# RTR_2T_LCD_CCS.net
KiCad netlist of a schematic drawn in EAGLE
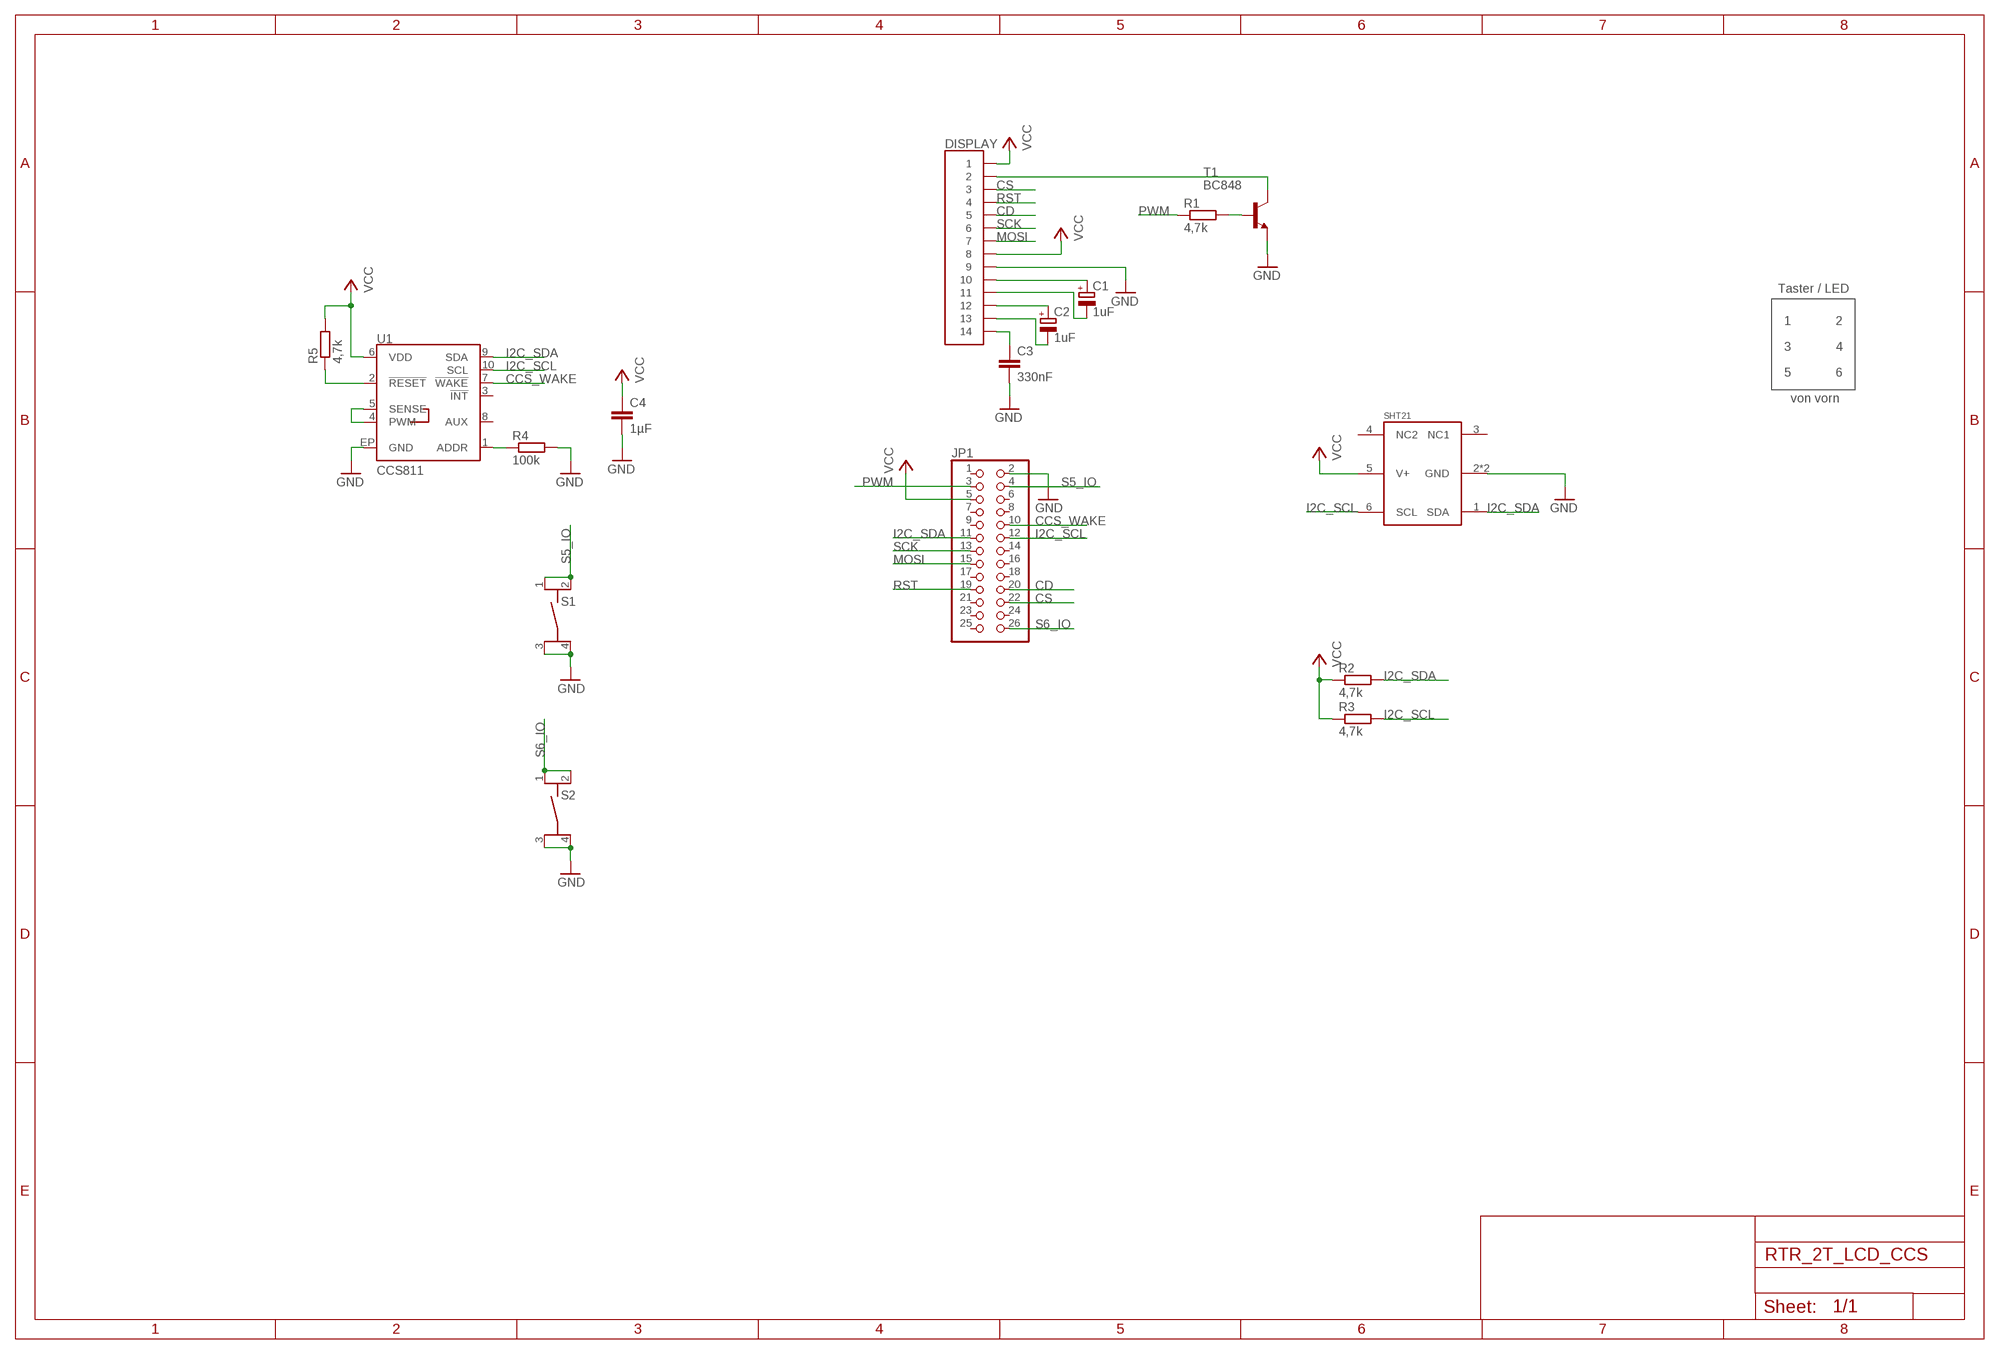
[diagram p0: schematic, sheet 1]

(export (version "E")
  (design (tool "Eeschema 10.0.6"))
  (components
    (comp (ref "C1")
      (value "1uF")
      (footprint "eagle-import:153CLV-0405")
      (libsource (lib "eagle-import") (part "CPOL-EU153CLV-0405"))
    )
    (comp (ref "C2")
      (value "1uF")
      (footprint "eagle-import:153CLV-0405")
      (libsource (lib "eagle-import") (part "CPOL-EU153CLV-0405"))
    )
    (comp (ref "C3")
      (value "330nF")
      (footprint "eagle-import:C0805")
      (libsource (lib "eagle-import") (part "C-EUC0805"))
    )
    (comp (ref "C4")
      (value "1µF")
      (footprint "eagle-import:C0805")
      (libsource (lib "eagle-import") (part "C-EUC0805"))
    )
    (comp (ref "DISPLAY")
      (value "FFC-14")
      (footprint "eagle-import:14-POLIG")
      (libsource (lib "eagle-import") (part "FFC-14"))
    )
    (comp (ref "JP1")
      (value "PINHD-2X13_2.54-SMD")
      (footprint "eagle-import:2X13SMD")
      (libsource (lib "eagle-import") (part "PINHD-2X13_2.54-SMD"))
    )
    (comp (ref "R1")
      (value "4,7k")
      (footprint "eagle-import:R0805")
      (libsource (lib "eagle-import") (part "R-EU_R0805"))
    )
    (comp (ref "R2")
      (value "4,7k")
      (footprint "eagle-import:R0805")
      (libsource (lib "eagle-import") (part "R-EU_R0805"))
    )
    (comp (ref "R3")
      (value "4,7k")
      (footprint "eagle-import:R0805")
      (libsource (lib "eagle-import") (part "R-EU_R0805"))
    )
    (comp (ref "R4")
      (value "100k")
      (footprint "eagle-import:R0805")
      (libsource (lib "eagle-import") (part "R-EU_R0805"))
    )
    (comp (ref "R5")
      (value "4,7k")
      (footprint "eagle-import:R0805")
      (libsource (lib "eagle-import") (part "R-EU_R0805"))
    )
    (comp (ref "S1")
      (value "TASTER_9314SMD")
      (footprint "eagle-import:TASTER_9314")
      (libsource (lib "eagle-import") (part "TASTER_9314SMD"))
    )
    (comp (ref "S2")
      (value "TASTER_9314SMD")
      (footprint "eagle-import:TASTER_9314")
      (libsource (lib "eagle-import") (part "TASTER_9314SMD"))
    )
    (comp (ref "SHT21")
      (value "SHT21")
      (footprint "eagle-import:SHT21")
      (libsource (lib "eagle-import") (part "SHT21"))
    )
    (comp (ref "T1")
      (value "BC848")
      (footprint "eagle-import:SOT23")
      (libsource (lib "eagle-import") (part "BC848"))
    )
    (comp (ref "U1")
      (value "CCS811")
      (footprint "eagle-import:LGA10")
      (libsource (lib "eagle-import") (part "CCS811"))
    )
  )
  (nets
    (net (code "1") (name "/CCS_WAKE") (class "Default")
      (node (ref "JP1") (pin "10") (pinfunction "10_10") (pintype "passive"))
      (node (ref "U1") (pin "7") (pinfunction "~{WAKE}_7") (pintype "bidirectional"))
    )
    (net (code "2") (name "/CD") (class "Default")
      (node (ref "DISPLAY") (pin "5") (pinfunction "5_5") (pintype "bidirectional"))
      (node (ref "JP1") (pin "20") (pinfunction "20_20") (pintype "passive"))
    )
    (net (code "3") (name "/CS") (class "Default")
      (node (ref "DISPLAY") (pin "3") (pinfunction "3_3") (pintype "bidirectional"))
      (node (ref "JP1") (pin "22") (pinfunction "22_22") (pintype "passive"))
    )
    (net (code "4") (name "/I2C_SCL") (class "Default")
      (node (ref "JP1") (pin "12") (pinfunction "12_12") (pintype "passive"))
      (node (ref "R3") (pin "2") (pinfunction "2_2") (pintype "passive"))
      (node (ref "SHT21") (pin "6") (pinfunction "SCL_6") (pintype "bidirectional"))
      (node (ref "U1") (pin "10") (pinfunction "SCL_10") (pintype "bidirectional"))
    )
    (net (code "5") (name "/I2C_SDA") (class "Default")
      (node (ref "JP1") (pin "11") (pinfunction "11_11") (pintype "passive"))
      (node (ref "R2") (pin "2") (pinfunction "2_2") (pintype "passive"))
      (node (ref "SHT21") (pin "1") (pinfunction "SDA_1") (pintype "bidirectional"))
      (node (ref "U1") (pin "9") (pinfunction "SDA_9") (pintype "bidirectional"))
    )
    (net (code "6") (name "/MOSI") (class "Default")
      (node (ref "DISPLAY") (pin "7") (pinfunction "7_7") (pintype "bidirectional"))
      (node (ref "JP1") (pin "15") (pinfunction "15_15") (pintype "passive"))
    )
    (net (code "7") (name "/PWM") (class "Default")
      (node (ref "JP1") (pin "3") (pinfunction "3_3") (pintype "passive"))
      (node (ref "R1") (pin "1") (pinfunction "1_1") (pintype "passive"))
    )
    (net (code "8") (name "/RST") (class "Default")
      (node (ref "DISPLAY") (pin "4") (pinfunction "4_4") (pintype "bidirectional"))
      (node (ref "JP1") (pin "19") (pinfunction "19_19") (pintype "passive"))
    )
    (net (code "9") (name "/S5_IO") (class "Default")
      (node (ref "JP1") (pin "4") (pinfunction "4_4") (pintype "passive"))
      (node (ref "S1") (pin "1") (pinfunction "1_1") (pintype "passive"))
      (node (ref "S1") (pin "2") (pinfunction "2_2") (pintype "passive"))
    )
    (net (code "10") (name "/S6_IO") (class "Default")
      (node (ref "JP1") (pin "26") (pinfunction "26_26") (pintype "passive"))
      (node (ref "S2") (pin "1") (pinfunction "1_1") (pintype "passive"))
      (node (ref "S2") (pin "2") (pinfunction "2_2") (pintype "passive"))
    )
    (net (code "11") (name "/SCK") (class "Default")
      (node (ref "DISPLAY") (pin "6") (pinfunction "6_6") (pintype "bidirectional"))
      (node (ref "JP1") (pin "13") (pinfunction "13_13") (pintype "passive"))
    )
    (net (code "12") (name "GND") (class "Default")
      (node (ref "C3") (pin "2") (pinfunction "2_2") (pintype "passive"))
      (node (ref "C4") (pin "2") (pinfunction "2_2") (pintype "passive"))
      (node (ref "DISPLAY") (pin "9") (pinfunction "9_9") (pintype "bidirectional"))
      (node (ref "JP1") (pin "2") (pinfunction "2_2") (pintype "passive"))
      (node (ref "R4") (pin "2") (pinfunction "2_2") (pintype "passive"))
      (node (ref "S1") (pin "3") (pinfunction "3_3") (pintype "passive"))
      (node (ref "S1") (pin "4") (pinfunction "4_4") (pintype "passive"))
      (node (ref "S2") (pin "3") (pinfunction "3_3") (pintype "passive"))
      (node (ref "S2") (pin "4") (pinfunction "4_4") (pintype "passive"))
      (node (ref "SHT21") (pin "2") (pinfunction "GND_2") (pintype "bidirectional"))
      (node (ref "SHT21") (pin "P$1") (pinfunction "GND_P$1") (pintype "bidirectional"))
      (node (ref "T1") (pin "2") (pinfunction "E_2") (pintype "passive"))
      (node (ref "U1") (pin "EP") (pinfunction "GND_EP") (pintype "bidirectional"))
    )
    (net (code "13") (name "Net-(C1-Pad+)") (class "Default")
      (node (ref "C1") (pin "+") (pinfunction "+_+") (pintype "passive"))
      (node (ref "DISPLAY") (pin "10") (pinfunction "10_10") (pintype "bidirectional"))
    )
    (net (code "14") (name "Net-(C1-Pad-)") (class "Default")
      (node (ref "C1") (pin "-") (pinfunction "-_-") (pintype "passive"))
      (node (ref "DISPLAY") (pin "11") (pinfunction "11_11") (pintype "bidirectional"))
    )
    (net (code "15") (name "Net-(C2-Pad+)") (class "Default")
      (node (ref "C2") (pin "+") (pinfunction "+_+") (pintype "passive"))
      (node (ref "DISPLAY") (pin "12") (pinfunction "12_12") (pintype "bidirectional"))
    )
    (net (code "16") (name "Net-(C2-Pad-)") (class "Default")
      (node (ref "C2") (pin "-") (pinfunction "-_-") (pintype "passive"))
      (node (ref "DISPLAY") (pin "13") (pinfunction "13_13") (pintype "bidirectional"))
    )
    (net (code "17") (name "Net-(C3-Pad1)") (class "Default")
      (node (ref "C3") (pin "1") (pinfunction "1_1") (pintype "passive"))
      (node (ref "DISPLAY") (pin "14") (pinfunction "14_14") (pintype "bidirectional"))
    )
    (net (code "18") (name "Net-(T1-B)") (class "Default")
      (node (ref "R1") (pin "2") (pinfunction "2_2") (pintype "passive"))
      (node (ref "T1") (pin "1") (pinfunction "B_1") (pintype "passive"))
    )
    (net (code "19") (name "Net-(T1-C)") (class "Default")
      (node (ref "DISPLAY") (pin "2") (pinfunction "2_2") (pintype "bidirectional"))
      (node (ref "T1") (pin "3") (pinfunction "C_3") (pintype "passive"))
    )
    (net (code "20") (name "Net-(U1-ADDR)") (class "Default")
      (node (ref "R4") (pin "1") (pinfunction "1_1") (pintype "passive"))
      (node (ref "U1") (pin "1") (pinfunction "ADDR_1") (pintype "bidirectional"))
    )
    (net (code "21") (name "Net-(U1-PWM)") (class "Default")
      (node (ref "U1") (pin "4") (pinfunction "PWM_4") (pintype "bidirectional"))
      (node (ref "U1") (pin "5") (pinfunction "SENSE_5") (pintype "bidirectional"))
    )
    (net (code "22") (name "Net-(U1-~{RESET})") (class "Default")
      (node (ref "R5") (pin "1") (pinfunction "1_1") (pintype "passive"))
      (node (ref "U1") (pin "2") (pinfunction "~{RESET}_2") (pintype "bidirectional"))
    )
    (net (code "23") (name "VCC") (class "Default")
      (node (ref "C4") (pin "1") (pinfunction "1_1") (pintype "passive"))
      (node (ref "DISPLAY") (pin "1") (pinfunction "1_1") (pintype "bidirectional"))
      (node (ref "DISPLAY") (pin "8") (pinfunction "8_8") (pintype "bidirectional"))
      (node (ref "JP1") (pin "5") (pinfunction "5_5") (pintype "passive"))
      (node (ref "R2") (pin "1") (pinfunction "1_1") (pintype "passive"))
      (node (ref "R3") (pin "1") (pinfunction "1_1") (pintype "passive"))
      (node (ref "R5") (pin "2") (pinfunction "2_2") (pintype "passive"))
      (node (ref "SHT21") (pin "5") (pinfunction "V+_5") (pintype "bidirectional"))
      (node (ref "U1") (pin "6") (pinfunction "VDD_6") (pintype "bidirectional"))
    )
    (net (code "24") (name "unconnected-(JP1-Pad1)") (class "Default")
      (node (ref "JP1") (pin "1") (pinfunction "1_1") (pintype "passive"))
    )
    (net (code "25") (name "unconnected-(JP1-Pad6)") (class "Default")
      (node (ref "JP1") (pin "6") (pinfunction "6_6") (pintype "passive"))
    )
    (net (code "26") (name "unconnected-(JP1-Pad7)") (class "Default")
      (node (ref "JP1") (pin "7") (pinfunction "7_7") (pintype "passive"))
    )
    (net (code "27") (name "unconnected-(JP1-Pad8)") (class "Default")
      (node (ref "JP1") (pin "8") (pinfunction "8_8") (pintype "passive"))
    )
    (net (code "28") (name "unconnected-(JP1-Pad9)") (class "Default")
      (node (ref "JP1") (pin "9") (pinfunction "9_9") (pintype "passive"))
    )
    (net (code "29") (name "unconnected-(JP1-Pad14)") (class "Default")
      (node (ref "JP1") (pin "14") (pinfunction "14_14") (pintype "passive"))
    )
    (net (code "30") (name "unconnected-(JP1-Pad16)") (class "Default")
      (node (ref "JP1") (pin "16") (pinfunction "16_16") (pintype "passive"))
    )
    (net (code "31") (name "unconnected-(JP1-Pad17)") (class "Default")
      (node (ref "JP1") (pin "17") (pinfunction "17_17") (pintype "passive"))
    )
    (net (code "32") (name "unconnected-(JP1-Pad18)") (class "Default")
      (node (ref "JP1") (pin "18") (pinfunction "18_18") (pintype "passive"))
    )
    (net (code "33") (name "unconnected-(JP1-Pad21)") (class "Default")
      (node (ref "JP1") (pin "21") (pinfunction "21_21") (pintype "passive"))
    )
    (net (code "34") (name "unconnected-(JP1-Pad23)") (class "Default")
      (node (ref "JP1") (pin "23") (pinfunction "23_23") (pintype "passive"))
    )
    (net (code "35") (name "unconnected-(JP1-Pad24)") (class "Default")
      (node (ref "JP1") (pin "24") (pinfunction "24_24") (pintype "passive"))
    )
    (net (code "36") (name "unconnected-(JP1-Pad25)") (class "Default")
      (node (ref "JP1") (pin "25") (pinfunction "25_25") (pintype "passive"))
    )
    (net (code "37") (name "unconnected-(SHT21-NC1-Pad3)") (class "Default")
      (node (ref "SHT21") (pin "3") (pinfunction "NC1_3") (pintype "bidirectional"))
    )
    (net (code "38") (name "unconnected-(SHT21-NC2-Pad4)") (class "Default")
      (node (ref "SHT21") (pin "4") (pinfunction "NC2_4") (pintype "bidirectional"))
    )
    (net (code "39") (name "unconnected-(U1-AUX-Pad8)") (class "Default")
      (node (ref "U1") (pin "8") (pinfunction "AUX_8") (pintype "bidirectional"))
    )
    (net (code "40") (name "unconnected-(U1-~{INT}-Pad3)") (class "Default")
      (node (ref "U1") (pin "3") (pinfunction "~{INT}_3") (pintype "bidirectional"))
    )
  )
)
